# pinbits.net
KiCad netlist of a schematic drawn in Altium Designer
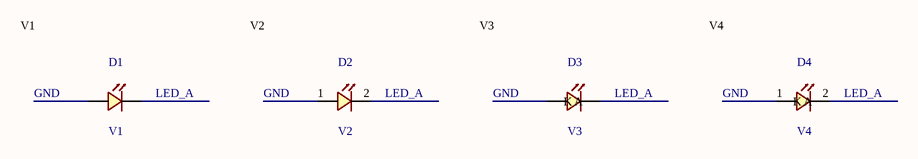
[diagram p0: pinbits.SchDoc]

(export (version "E")
  (design (tool "Eeschema 10.0.6"))
  (components
    (comp (ref "D1") (value "V1") (libsource (lib "pinbits") (part "LED_V1")))
    (comp (ref "D2") (value "V2") (libsource (lib "pinbits") (part "LED_V2")))
    (comp (ref "D3") (value "V3") (libsource (lib "pinbits") (part "LED_V3")))
    (comp (ref "D4") (value "V4") (libsource (lib "pinbits") (part "LED_V4")))
  )
  (nets
    (net (code "1") (name "/GND") (class "Default")
      (node (ref "D1") (pin "1") (pinfunction "A_1") (pintype "passive"))
      (node (ref "D2") (pin "1") (pinfunction "A_1") (pintype "passive"))
      (node (ref "D3") (pin "1") (pinfunction "A_1") (pintype "passive"))
      (node (ref "D4") (pin "1") (pinfunction "A_1") (pintype "passive"))
    )
    (net (code "2") (name "/LED_A") (class "Default")
      (node (ref "D1") (pin "2") (pinfunction "K_2") (pintype "passive"))
      (node (ref "D2") (pin "2") (pinfunction "K_2") (pintype "passive"))
      (node (ref "D3") (pin "2") (pinfunction "K_2") (pintype "passive"))
      (node (ref "D4") (pin "2") (pinfunction "K_2") (pintype "passive"))
    )
  )
)
